# WaveGenerator.net
KiCad netlist of a schematic drawn in Altium Designer
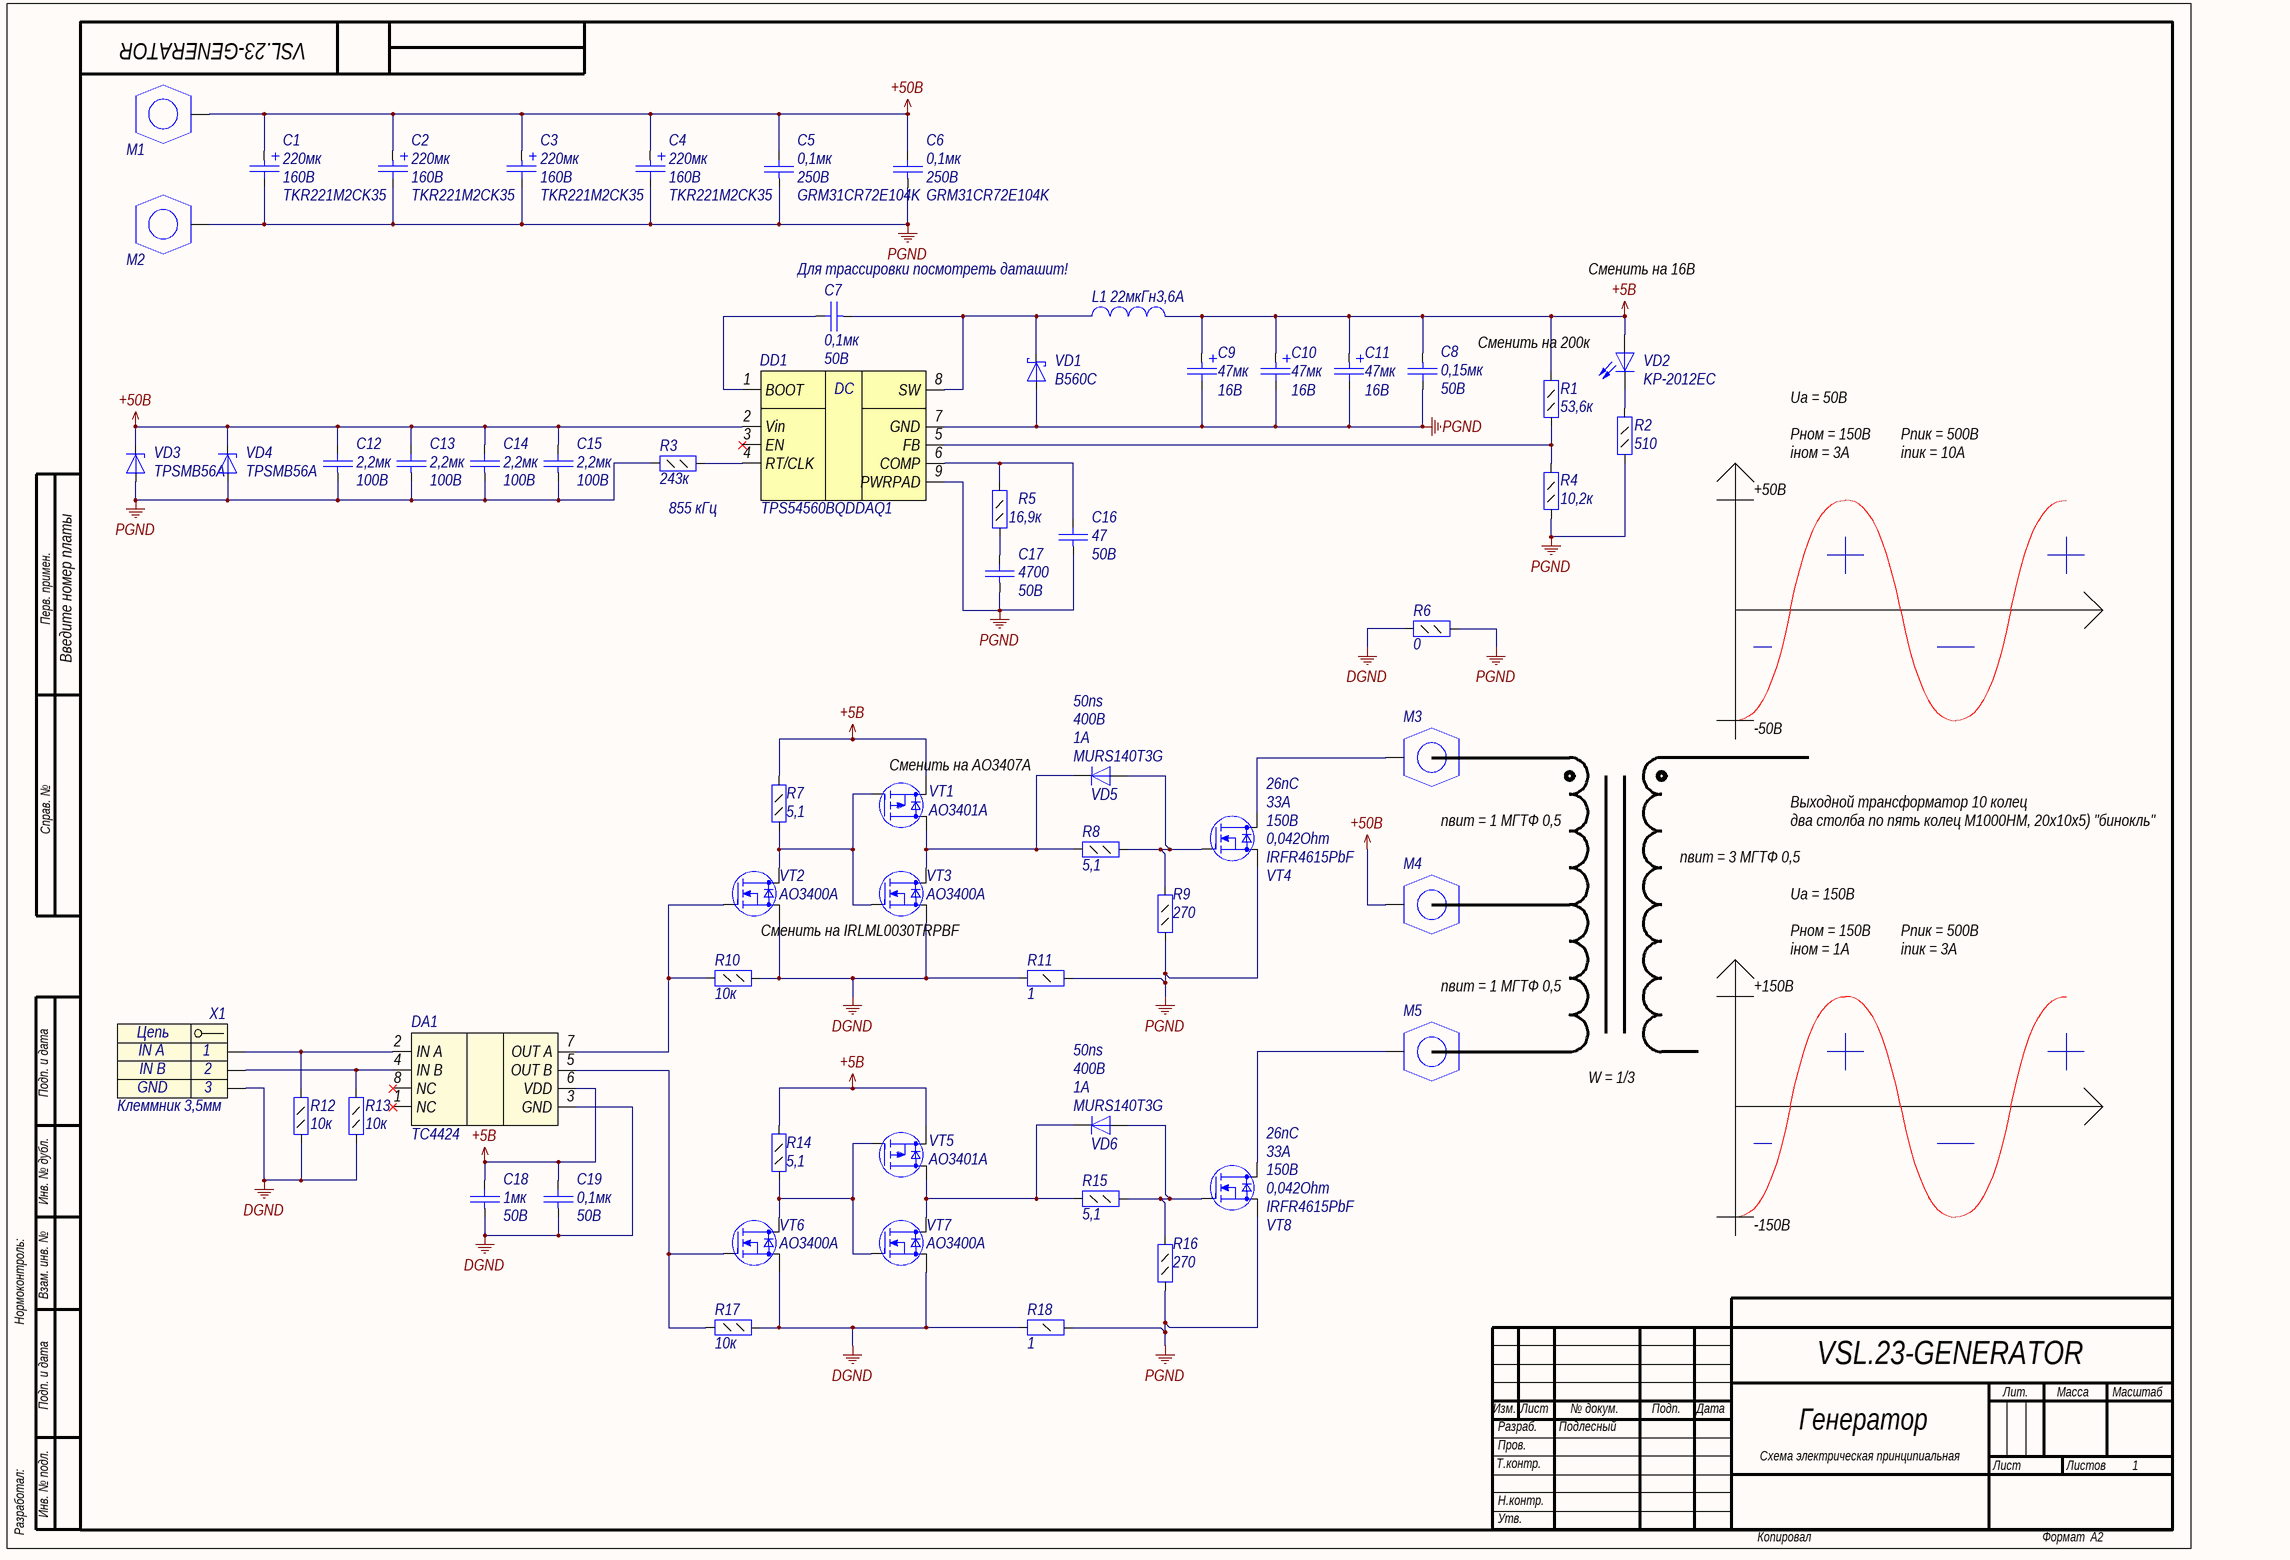
[diagram p0: WaveGenerator.SchDoc]

(export (version "E")
  (design (tool "Eeschema 10.0.6"))
  (components
    (comp (ref "C1")
      (value "220мк")
      (footprint "K50-35(16X35)_V")
      (description "Конденсатор полярный")
      (fields
        (field (name "VOLTAGE") "160B")
        (field (name "PART NUMBER") "TKR221M2CK35")
        (field (name "Comment") "Capacitor_pol")
      )
      (libsource (lib "MOP44") (part "Capacitor_pol"))
    )
    (comp (ref "C2")
      (value "220мк")
      (footprint "K50-35(16X35)_V")
      (description "Конденсатор полярный")
      (fields
        (field (name "VOLTAGE") "160B")
        (field (name "PART NUMBER") "TKR221M2CK35")
        (field (name "Comment") "Capacitor_pol")
      )
      (libsource (lib "MOP44") (part "Capacitor_pol"))
    )
    (comp (ref "C3")
      (value "220мк")
      (footprint "K50-35(16X35)_V")
      (description "Конденсатор полярный")
      (fields
        (field (name "VOLTAGE") "160B")
        (field (name "PART NUMBER") "TKR221M2CK35")
        (field (name "Comment") "Capacitor_pol")
      )
      (libsource (lib "MOP44") (part "Capacitor_pol"))
    )
    (comp (ref "C4")
      (value "220мк")
      (footprint "K50-35(16X35)_V")
      (description "Конденсатор полярный")
      (fields
        (field (name "VOLTAGE") "160B")
        (field (name "PART NUMBER") "TKR221M2CK35")
        (field (name "Comment") "Capacitor_pol")
      )
      (libsource (lib "MOP44") (part "Capacitor_pol"))
    )
    (comp (ref "C5")
      (value "0,1мк")
      (footprint "C1206")
      (description "Конденсатор")
      (fields (field (name "VOLTAGE") "250В") (field (name "PART NUMBER") "GRM31CR72E104K"))
      (libsource (lib "MOP44") (part "Capacitor"))
    )
    (comp (ref "C6")
      (value "0,1мк")
      (footprint "C1206")
      (description "Конденсатор")
      (fields (field (name "VOLTAGE") "250В") (field (name "PART NUMBER") "GRM31CR72E104K"))
      (libsource (lib "MOP44") (part "Capacitor"))
    )
    (comp (ref "C7")
      (value "0,1мк")
      (footprint "C0402")
      (description "Конденсатор")
      (fields (field (name "VOLTAGE") "50В") (field (name "PART NUMBER") "GRM155R71H104KE14D"))
      (libsource (lib "MOP44") (part "Capacitor"))
    )
    (comp (ref "C8")
      (value "0,15мк")
      (footprint "C1812")
      (description "Конденсатор")
      (fields (field (name "VOLTAGE") "50В") (field (name "PART NUMBER") "C4532C0G1H154J250KA"))
      (libsource (lib "MOP44") (part "Capacitor"))
    )
    (comp (ref "C9")
      (value "47мк")
      (footprint "TANTAL CASE C")
      (description "Конденсатор полярный")
      (fields
        (field (name "VOLTAGE") "16В")
        (field (name "PART NUMBER") "TECAP47/16VC10")
        (field (name "Comment") "Capacitor_pol")
      )
      (libsource (lib "MOP44") (part "Capacitor_pol"))
    )
    (comp (ref "C10")
      (value "47мк")
      (footprint "TANTAL CASE C")
      (description "Конденсатор полярный")
      (fields
        (field (name "VOLTAGE") "16В")
        (field (name "PART NUMBER") "TECAP47/16VC10")
        (field (name "Comment") "Capacitor_pol")
      )
      (libsource (lib "MOP44") (part "Capacitor_pol"))
    )
    (comp (ref "C11")
      (value "47мк")
      (footprint "TANTAL CASE C")
      (description "Конденсатор полярный")
      (fields
        (field (name "VOLTAGE") "16В")
        (field (name "PART NUMBER") "TECAP47/16VC10")
        (field (name "Comment") "Capacitor_pol")
      )
      (libsource (lib "MOP44") (part "Capacitor_pol"))
    )
    (comp (ref "C12")
      (value "2,2мк")
      (footprint "C1812")
      (description "Конденсатор")
      (fields (field (name "VOLTAGE") "100В") (field (name "PART NUMBER") "C4532X7R2A225M"))
      (libsource (lib "MOP44") (part "Capacitor"))
    )
    (comp (ref "C13")
      (value "2,2мк")
      (footprint "C1812")
      (description "Конденсатор")
      (fields (field (name "VOLTAGE") "100В") (field (name "PART NUMBER") "C4532X7R2A225M"))
      (libsource (lib "MOP44") (part "Capacitor"))
    )
    (comp (ref "C14")
      (value "2,2мк")
      (footprint "C1812")
      (description "Конденсатор")
      (fields (field (name "VOLTAGE") "100В") (field (name "PART NUMBER") "C4532X7R2A225M"))
      (libsource (lib "MOP44") (part "Capacitor"))
    )
    (comp (ref "C15")
      (value "2,2мк")
      (footprint "C1812")
      (description "Конденсатор")
      (fields (field (name "VOLTAGE") "100В") (field (name "PART NUMBER") "C4532X7R2A225M"))
      (libsource (lib "MOP44") (part "Capacitor"))
    )
    (comp (ref "C16")
      (value "47")
      (footprint "C0805")
      (description "Конденсатор")
      (fields (field (name "VOLTAGE") "50В") (field (name "PART NUMBER") "GRM2165C1H470JD01D"))
      (libsource (lib "MOP44") (part "Capacitor"))
    )
    (comp (ref "C17")
      (value "4700")
      (footprint "C0805")
      (description "Конденсатор")
      (fields (field (name "VOLTAGE") "50В") (field (name "PART NUMBER") "GRM216R71H472K"))
      (libsource (lib "MOP44") (part "Capacitor"))
    )
    (comp (ref "C18")
      (value "1мк")
      (footprint "C0805")
      (description "Конденсатор")
      (fields (field (name "VOLTAGE") "50B") (field (name "PART NUMBER") "GRM21BR71H105K"))
      (libsource (lib "MOP44") (part "Capacitor"))
    )
    (comp (ref "C19")
      (value "0,1мк")
      (footprint "C0805")
      (description "Конденсатор")
      (fields (field (name "VOLTAGE") "50В") (field (name "PART NUMBER") "GRM21BR71H104KA01L"))
      (libsource (lib "MOP44") (part "Capacitor"))
    )
    (comp (ref "DA1")
      (value "TC4424")
      (footprint "DIP8")
      (description "3A Dual High-Speed Power MOSFET Drivers")
      (fields (field (name "PART NUMBER") "TC4424CPA"))
      (libsource (lib "MOP44") (part "TC4424"))
    )
    (comp (ref "DD1")
      (value "TPS54560")
      (footprint "SO Powerpad8")
      (description "5-A, Wide Input Range, Step-Down Converter")
      (fields
        (field (name "PART NUMBER") "TPS54560BQDDAQ1")
        (field (name "MANUFACTURER") "Texas Instruments")
      )
      (libsource (lib "MOP44") (part "TPS54560"))
    )
    (comp (ref "L1")
      (value "22мкГн")
      (footprint "IND_12.5x12.5")
      (description "EMI Suppression Filter")
      (fields
        (field (name "RATED CURRENT") "3,6A")
        (field (name "PART NUMBER") "B82477G4223M000")
        (field (name "Comment") "Inductor")
      )
      (libsource (lib "MOP44") (part "Inductor"))
    )
    (comp (ref "M1") (value "SCREW") (footprint "SCREW2.5") (libsource (lib "MOP44") (part "SCREW")))
    (comp (ref "M2") (value "SCREW") (footprint "SCREW2.5") (libsource (lib "MOP44") (part "SCREW")))
    (comp (ref "M3") (value "SCREW") (footprint "SCREW2.5") (libsource (lib "MOP44") (part "SCREW")))
    (comp (ref "M4") (value "SCREW") (footprint "SCREW2.5") (libsource (lib "MOP44") (part "SCREW")))
    (comp (ref "M5") (value "SCREW") (footprint "SCREW2.5") (libsource (lib "MOP44") (part "SCREW")))
    (comp (ref "R1")
      (value "53,6к")
      (footprint "R0805")
      (description "Резистор")
      (fields (field (name "PART NUMBER") "RC0805FR-0753K6L") (field (name "POWER") "0,125Вт"))
      (libsource (lib "MOP44") (part "Resistor_0,125Вт"))
    )
    (comp (ref "R2")
      (value "510")
      (footprint "R0805")
      (description "Резистор")
      (fields (field (name "PART NUMBER") "RC0805FR-07510RL") (field (name "POWER") "0,125Вт"))
      (libsource (lib "MOP44") (part "Resistor_0,125Вт"))
    )
    (comp (ref "R3")
      (value "243к")
      (footprint "R0805")
      (description "Резистор")
      (fields (field (name "PART NUMBER") "RC0805FR-07243KL") (field (name "POWER") "0,125Вт"))
      (libsource (lib "") (part "Resistor_0,125Вт_2"))
    )
    (comp (ref "R4")
      (value "10,2к")
      (footprint "R0805")
      (description "Резистор")
      (fields (field (name "PART NUMBER") "RC0805FR-0710K2L") (field (name "POWER") "0,125Вт"))
      (libsource (lib "MOP44") (part "Resistor_0,125Вт"))
    )
    (comp (ref "R5")
      (value "16,9к")
      (footprint "R0805")
      (description "Резистор")
      (fields (field (name "PART NUMBER") "RC0805FR-0716K9L") (field (name "POWER") "0,125Вт"))
      (libsource (lib "MOP44") (part "Resistor_0,125Вт"))
    )
    (comp (ref "R6")
      (value "0")
      (footprint "R0805")
      (description "Резистор")
      (fields (field (name "PART NUMBER") "RC0805FR-070RL") (field (name "POWER") "0,125Вт"))
      (libsource (lib "") (part "Resistor_0,125Вт_2"))
    )
    (comp (ref "R7")
      (value "5,1")
      (footprint "R0805")
      (description "Резистор")
      (fields (field (name "PART NUMBER") "RC0805FR-075R1L") (field (name "POWER") "0,125Вт"))
      (libsource (lib "MOP44") (part "Resistor_0,125Вт"))
    )
    (comp (ref "R8")
      (value "5,1")
      (footprint "R0805")
      (description "Резистор")
      (fields (field (name "PART NUMBER") "RC0805FR-075R1L") (field (name "POWER") "0,125Вт"))
      (libsource (lib "") (part "Resistor_0,125Вт_2"))
    )
    (comp (ref "R9")
      (value "270")
      (footprint "R0805")
      (description "Резистор")
      (fields (field (name "PART NUMBER") "RC0805FR-07270RL") (field (name "POWER") "0,125Вт"))
      (libsource (lib "MOP44") (part "Resistor_0,125Вт"))
    )
    (comp (ref "R10")
      (value "10к")
      (footprint "R0805")
      (description "Резистор")
      (fields (field (name "PART NUMBER") "RC0805FR-0710KL") (field (name "POWER") "0,125Вт"))
      (libsource (lib "") (part "Resistor_0,125Вт_1"))
    )
    (comp (ref "R11")
      (value "1")
      (footprint "R1206")
      (description "Резистор")
      (fields (field (name "PART NUMBER") "RC1206FR-071RL") (field (name "POWER") "0,25Вт"))
      (libsource (lib "MOP44") (part "Resistor_0,25Вт"))
    )
    (comp (ref "R12")
      (value "10к")
      (footprint "R0805")
      (description "Резистор")
      (fields (field (name "PART NUMBER") "RC0805FR-0710KL") (field (name "POWER") "0,125Вт"))
      (libsource (lib "MOP44") (part "Resistor_0,125Вт"))
    )
    (comp (ref "R13")
      (value "10к")
      (footprint "R0805")
      (description "Резистор")
      (fields (field (name "PART NUMBER") "RC0805FR-0710KL") (field (name "POWER") "0,125Вт"))
      (libsource (lib "MOP44") (part "Resistor_0,125Вт"))
    )
    (comp (ref "R14")
      (value "5,1")
      (footprint "R0805")
      (description "Резистор")
      (fields (field (name "PART NUMBER") "RC0805FR-075R1L") (field (name "POWER") "0,125Вт"))
      (libsource (lib "MOP44") (part "Resistor_0,125Вт"))
    )
    (comp (ref "R15")
      (value "5,1")
      (footprint "R0805")
      (description "Резистор")
      (fields (field (name "PART NUMBER") "RC0805FR-075R1L") (field (name "POWER") "0,125Вт"))
      (libsource (lib "") (part "Resistor_0,125Вт_2"))
    )
    (comp (ref "R16")
      (value "270")
      (footprint "R0805")
      (description "Резистор")
      (fields (field (name "PART NUMBER") "RC0805FR-07270RL") (field (name "POWER") "0,125Вт"))
      (libsource (lib "MOP44") (part "Resistor_0,125Вт"))
    )
    (comp (ref "R17")
      (value "10к")
      (footprint "R0805")
      (description "Резистор")
      (fields (field (name "PART NUMBER") "RC0805FR-0710KL") (field (name "POWER") "0,125Вт"))
      (libsource (lib "") (part "Resistor_0,125Вт_1"))
    )
    (comp (ref "R18")
      (value "1")
      (footprint "R1206")
      (description "Резистор")
      (fields (field (name "PART NUMBER") "RC1206FR-071RL") (field (name "POWER") "0,25Вт"))
      (libsource (lib "MOP44") (part "Resistor_0,25Вт"))
    )
    (comp (ref "VD1")
      (value "DiodeSchottky")
      (footprint "SMC")
      (description "Диод Шоттки")
      (fields (field (name "PART NUMBER") "B560C"))
      (libsource (lib "MOP44") (part "DiodeSchottky"))
    )
    (comp (ref "VD2")
      (value "LED")
      (footprint "L_0805")
      (description "Светодиод")
      (fields (field (name "PART NUMBER") "KP-2012EC"))
      (libsource (lib "MOP44") (part "LED"))
    )
    (comp (ref "VD3")
      (value "DiodeZener")
      (footprint "SMB")
      (description "Cтабилитрон (лавинный выпрямительный диод) односторонний")
      (fields (field (name "PART NUMBER") "TPSMB56A"))
      (libsource (lib "MOP44") (part "DiodeZener"))
    )
    (comp (ref "VD4")
      (value "DiodeZener")
      (footprint "SMB")
      (description "Cтабилитрон (лавинный выпрямительный диод) односторонний")
      (fields (field (name "PART NUMBER") "TPSMB56A"))
      (libsource (lib "MOP44") (part "DiodeZener"))
    )
    (comp (ref "VD5")
      (value "Diode")
      (footprint "SMB")
      (description "Диод")
      (fields
        (field (name "FORWARD CURRENT") "1A")
        (field (name "BREAKDOWN VOLTAGE") "400B")
        (field (name "REVERSE RECOVERY TIME") "50ns")
        (field (name "PART NUMBER") "MURS140T3G")
      )
      (libsource (lib "MOP44") (part "Diode"))
    )
    (comp (ref "VD6")
      (value "Diode")
      (footprint "SMB")
      (description "Диод")
      (fields
        (field (name "FORWARD CURRENT") "1A")
        (field (name "BREAKDOWN VOLTAGE") "400B")
        (field (name "REVERSE RECOVERY TIME") "50ns")
        (field (name "PART NUMBER") "MURS140T3G")
      )
      (libsource (lib "MOP44") (part "Diode"))
    )
    (comp (ref "VT1")
      (value "P-MOSFET")
      (footprint "SOT23-3")
      (description "N-MOSFET")
      (fields (field (name "PART NUMBER") "AO3401A") (field (name "MANUFACTURER") "Alpha&Omega"))
      (libsource (lib "MOP44") (part "P-MOSFET"))
    )
    (comp (ref "VT2")
      (value "N-MOSFET")
      (footprint "SOT23-3")
      (fields (field (name "PART NUMBER") "AO3400A") (field (name "MANUFACTURER") "Alpha&Omega"))
      (libsource (lib "MOP44") (part "N-MOSFET"))
    )
    (comp (ref "VT3")
      (value "N-MOSFET")
      (footprint "SOT23-3")
      (fields (field (name "PART NUMBER") "AO3400A") (field (name "MANUFACTURER") "Alpha&Omega"))
      (libsource (lib "MOP44") (part "N-MOSFET"))
    )
    (comp (ref "VT4")
      (value "N-MOSFET")
      (footprint "DPAK")
      (fields
        (field (name "V DRAIN-SOURCE MAX") "150B")
        (field (name "RDS") "0,042Ohm")
        (field (name "CONTINUOUS DRAIN CURRENT") "33A")
        (field (name "TOTAL GATE CHARGE") "26nC")
        (field (name "PART NUMBER") "IRFR4615PbF")
        (field (name "MANUFACTURER") "International Rectifier")
      )
      (libsource (lib "MOP44") (part "N-MOSFET"))
    )
    (comp (ref "VT5")
      (value "P-MOSFET")
      (footprint "SOT23-3")
      (description "N-MOSFET")
      (fields (field (name "PART NUMBER") "AO3401A") (field (name "MANUFACTURER") "Alpha&Omega"))
      (libsource (lib "MOP44") (part "P-MOSFET"))
    )
    (comp (ref "VT6")
      (value "N-MOSFET")
      (footprint "SOT23-3")
      (fields (field (name "PART NUMBER") "AO3400A") (field (name "MANUFACTURER") "Alpha&Omega"))
      (libsource (lib "MOP44") (part "N-MOSFET"))
    )
    (comp (ref "VT7")
      (value "N-MOSFET")
      (footprint "SOT23-3")
      (fields (field (name "PART NUMBER") "AO3400A") (field (name "MANUFACTURER") "Alpha&Omega"))
      (libsource (lib "MOP44") (part "N-MOSFET"))
    )
    (comp (ref "VT8")
      (value "N-MOSFET")
      (footprint "DPAK")
      (fields
        (field (name "V DRAIN-SOURCE MAX") "150B")
        (field (name "RDS") "0,042Ohm")
        (field (name "CONTINUOUS DRAIN CURRENT") "33A")
        (field (name "TOTAL GATE CHARGE") "26nC")
        (field (name "PART NUMBER") "IRFR4615PbF")
        (field (name "MANUFACTURER") "International Rectifier")
      )
      (libsource (lib "MOP44") (part "N-MOSFET"))
    )
    (comp (ref "X1")
      (value "Клеммник 3,5мм")
      (footprint "TERMINAL-3WAY-3.5MM")
      (description "Разъем - 3 конт. клеммник")
      (libsource (lib "MOP44") (part "Header_3_trm"))
    )
  )
  (nets
    (net (code "1") (name "+5B") (class "Default")
      (node (ref "C10") (pin "1") (pinfunction "1_1") (pintype "passive"))
      (node (ref "C11") (pin "1") (pinfunction "1_1") (pintype "passive"))
      (node (ref "C18") (pin "2") (pinfunction "2_2") (pintype "passive"))
      (node (ref "C19") (pin "2") (pinfunction "2_2") (pintype "passive"))
      (node (ref "C8") (pin "1") (pinfunction "1_1") (pintype "passive"))
      (node (ref "C9") (pin "1") (pinfunction "1_1") (pintype "passive"))
      (node (ref "DA1") (pin "6") (pinfunction "VDD_6") (pintype "passive"))
      (node (ref "L1") (pin "2") (pinfunction "2_2") (pintype "passive"))
      (node (ref "R1") (pin "2") (pinfunction "2_2") (pintype "passive"))
      (node (ref "R14") (pin "2") (pinfunction "2_2") (pintype "passive"))
      (node (ref "R7") (pin "2") (pinfunction "2_2") (pintype "passive"))
      (node (ref "VD2") (pin "2") (pinfunction "A_2") (pintype "passive"))
      (node (ref "VT1") (pin "3") (pinfunction "S_3") (pintype "passive"))
      (node (ref "VT5") (pin "3") (pinfunction "S_3") (pintype "passive"))
    )
    (net (code "2") (name "+50B") (class "Default")
      (node (ref "C1") (pin "1") (pinfunction "1_1") (pintype "passive"))
      (node (ref "C12") (pin "2") (pinfunction "2_2") (pintype "passive"))
      (node (ref "C13") (pin "2") (pinfunction "2_2") (pintype "passive"))
      (node (ref "C14") (pin "2") (pinfunction "2_2") (pintype "passive"))
      (node (ref "C15") (pin "2") (pinfunction "2_2") (pintype "passive"))
      (node (ref "C2") (pin "1") (pinfunction "1_1") (pintype "passive"))
      (node (ref "C3") (pin "1") (pinfunction "1_1") (pintype "passive"))
      (node (ref "C4") (pin "1") (pinfunction "1_1") (pintype "passive"))
      (node (ref "C5") (pin "2") (pinfunction "2_2") (pintype "passive"))
      (node (ref "C6") (pin "2") (pinfunction "2_2") (pintype "passive"))
      (node (ref "DD1") (pin "2") (pinfunction "Vin_2") (pintype "passive"))
      (node (ref "M1") (pin "1") (pinfunction "1_1") (pintype "passive"))
      (node (ref "M4") (pin "1") (pinfunction "1_1") (pintype "passive"))
      (node (ref "VD3") (pin "1") (pinfunction "K_1") (pintype "passive"))
      (node (ref "VD4") (pin "1") (pinfunction "K_1") (pintype "passive"))
    )
    (net (code "3") (name "DGND") (class "Default")
      (node (ref "C18") (pin "1") (pinfunction "1_1") (pintype "passive"))
      (node (ref "C19") (pin "1") (pinfunction "1_1") (pintype "passive"))
      (node (ref "DA1") (pin "3") (pinfunction "GND_3") (pintype "passive"))
      (node (ref "R10") (pin "1") (pinfunction "1_1") (pintype "passive"))
      (node (ref "R11") (pin "1") (pinfunction "1_1") (pintype "passive"))
      (node (ref "R12") (pin "1") (pinfunction "1_1") (pintype "passive"))
      (node (ref "R13") (pin "1") (pinfunction "1_1") (pintype "passive"))
      (node (ref "R17") (pin "1") (pinfunction "1_1") (pintype "passive"))
      (node (ref "R18") (pin "1") (pinfunction "1_1") (pintype "passive"))
      (node (ref "R6") (pin "1") (pinfunction "1_1") (pintype "passive"))
      (node (ref "VT2") (pin "3") (pinfunction "S_3") (pintype "passive"))
      (node (ref "VT3") (pin "3") (pinfunction "S_3") (pintype "passive"))
      (node (ref "VT6") (pin "3") (pinfunction "S_3") (pintype "passive"))
      (node (ref "VT7") (pin "3") (pinfunction "S_3") (pintype "passive"))
      (node (ref "X1") (pin "3") (pinfunction "3_3") (pintype "passive"))
    )
    (net (code "4") (name "Net-(C17-Pad2)") (class "Default")
      (node (ref "C17") (pin "2") (pinfunction "2_2") (pintype "passive"))
      (node (ref "R5") (pin "1") (pinfunction "1_1") (pintype "passive"))
    )
    (net (code "5") (name "Net-(DA1-IN_A)") (class "Default")
      (node (ref "DA1") (pin "2") (pinfunction "IN_A_2") (pintype "passive"))
      (node (ref "R12") (pin "2") (pinfunction "2_2") (pintype "passive"))
      (node (ref "X1") (pin "1") (pinfunction "1_1") (pintype "passive"))
    )
    (net (code "6") (name "Net-(DA1-IN_B)") (class "Default")
      (node (ref "DA1") (pin "4") (pinfunction "IN_B_4") (pintype "passive"))
      (node (ref "R13") (pin "2") (pinfunction "2_2") (pintype "passive"))
      (node (ref "X1") (pin "2") (pinfunction "2_2") (pintype "passive"))
    )
    (net (code "7") (name "Net-(DA1-OUT_A)") (class "Default")
      (node (ref "DA1") (pin "7") (pinfunction "OUT_A_7") (pintype "passive"))
      (node (ref "R10") (pin "2") (pinfunction "2_2") (pintype "passive"))
      (node (ref "VT2") (pin "1") (pinfunction "G_1") (pintype "passive"))
    )
    (net (code "8") (name "Net-(DA1-OUT_B)") (class "Default")
      (node (ref "DA1") (pin "5") (pinfunction "OUT_B_5") (pintype "passive"))
      (node (ref "R17") (pin "2") (pinfunction "2_2") (pintype "passive"))
      (node (ref "VT6") (pin "1") (pinfunction "G_1") (pintype "passive"))
    )
    (net (code "9") (name "Net-(DD1-BOOT)") (class "Default")
      (node (ref "C7") (pin "2") (pinfunction "2_2") (pintype "passive"))
      (node (ref "DD1") (pin "1") (pinfunction "BOOT_1") (pintype "passive"))
    )
    (net (code "10") (name "Net-(DD1-COMP)") (class "Default")
      (node (ref "C16") (pin "2") (pinfunction "2_2") (pintype "passive"))
      (node (ref "DD1") (pin "6") (pinfunction "COMP_6") (pintype "passive"))
      (node (ref "R5") (pin "2") (pinfunction "2_2") (pintype "passive"))
    )
    (net (code "11") (name "Net-(DD1-FB)") (class "Default")
      (node (ref "DD1") (pin "5") (pinfunction "FB_5") (pintype "passive"))
      (node (ref "R1") (pin "1") (pinfunction "1_1") (pintype "passive"))
      (node (ref "R4") (pin "2") (pinfunction "2_2") (pintype "passive"))
    )
    (net (code "12") (name "Net-(DD1-RT{slash}CLK)") (class "Default")
      (node (ref "DD1") (pin "4") (pinfunction "RT/CLK_4") (pintype "passive"))
      (node (ref "R3") (pin "2") (pinfunction "2_2") (pintype "passive"))
    )
    (net (code "13") (name "Net-(DD1-SW)") (class "Default")
      (node (ref "C7") (pin "1") (pinfunction "1_1") (pintype "passive"))
      (node (ref "DD1") (pin "8") (pinfunction "SW_8") (pintype "passive"))
      (node (ref "L1") (pin "1") (pinfunction "1_1") (pintype "passive"))
      (node (ref "VD1") (pin "1") (pinfunction "K_1") (pintype "passive"))
    )
    (net (code "14") (name "Net-(VD2-K)") (class "Default")
      (node (ref "R2") (pin "2") (pinfunction "2_2") (pintype "passive"))
      (node (ref "VD2") (pin "1") (pinfunction "K_1") (pintype "passive"))
    )
    (net (code "15") (name "Net-(VD5-A)") (class "Default")
      (node (ref "R8") (pin "2") (pinfunction "2_2") (pintype "passive"))
      (node (ref "R9") (pin "2") (pinfunction "2_2") (pintype "passive"))
      (node (ref "VD5") (pin "2") (pinfunction "A_2") (pintype "passive"))
      (node (ref "VT4") (pin "1") (pinfunction "G_1") (pintype "passive"))
    )
    (net (code "16") (name "Net-(VD5-K)") (class "Default")
      (node (ref "R8") (pin "1") (pinfunction "1_1") (pintype "passive"))
      (node (ref "VD5") (pin "1") (pinfunction "K_1") (pintype "passive"))
      (node (ref "VT1") (pin "2") (pinfunction "D_2") (pintype "passive"))
      (node (ref "VT3") (pin "2") (pinfunction "D_2") (pintype "passive"))
    )
    (net (code "17") (name "Net-(VD6-A)") (class "Default")
      (node (ref "R15") (pin "2") (pinfunction "2_2") (pintype "passive"))
      (node (ref "R16") (pin "2") (pinfunction "2_2") (pintype "passive"))
      (node (ref "VD6") (pin "2") (pinfunction "A_2") (pintype "passive"))
      (node (ref "VT8") (pin "1") (pinfunction "G_1") (pintype "passive"))
    )
    (net (code "18") (name "Net-(VD6-K)") (class "Default")
      (node (ref "R15") (pin "1") (pinfunction "1_1") (pintype "passive"))
      (node (ref "VD6") (pin "1") (pinfunction "K_1") (pintype "passive"))
      (node (ref "VT5") (pin "2") (pinfunction "D_2") (pintype "passive"))
      (node (ref "VT7") (pin "2") (pinfunction "D_2") (pintype "passive"))
    )
    (net (code "19") (name "Net-(VT1-G)") (class "Default")
      (node (ref "R7") (pin "1") (pinfunction "1_1") (pintype "passive"))
      (node (ref "VT1") (pin "1") (pinfunction "G_1") (pintype "passive"))
      (node (ref "VT2") (pin "2") (pinfunction "D_2") (pintype "passive"))
      (node (ref "VT3") (pin "1") (pinfunction "G_1") (pintype "passive"))
    )
    (net (code "20") (name "Net-(VT4-D)") (class "Default")
      (node (ref "M3") (pin "1") (pinfunction "1_1") (pintype "passive"))
      (node (ref "VT4") (pin "2") (pinfunction "D_2") (pintype "passive"))
    )
    (net (code "21") (name "Net-(VT5-G)") (class "Default")
      (node (ref "R14") (pin "1") (pinfunction "1_1") (pintype "passive"))
      (node (ref "VT5") (pin "1") (pinfunction "G_1") (pintype "passive"))
      (node (ref "VT6") (pin "2") (pinfunction "D_2") (pintype "passive"))
      (node (ref "VT7") (pin "1") (pinfunction "G_1") (pintype "passive"))
    )
    (net (code "22") (name "Net-(VT8-D)") (class "Default")
      (node (ref "M5") (pin "1") (pinfunction "1_1") (pintype "passive"))
      (node (ref "VT8") (pin "2") (pinfunction "D_2") (pintype "passive"))
    )
    (net (code "23") (name "PGND") (class "Default")
      (node (ref "C1") (pin "2") (pinfunction "2_2") (pintype "passive"))
      (node (ref "C10") (pin "2") (pinfunction "2_2") (pintype "passive"))
      (node (ref "C11") (pin "2") (pinfunction "2_2") (pintype "passive"))
      (node (ref "C12") (pin "1") (pinfunction "1_1") (pintype "passive"))
      (node (ref "C13") (pin "1") (pinfunction "1_1") (pintype "passive"))
      (node (ref "C14") (pin "1") (pinfunction "1_1") (pintype "passive"))
      (node (ref "C15") (pin "1") (pinfunction "1_1") (pintype "passive"))
      (node (ref "C16") (pin "1") (pinfunction "1_1") (pintype "passive"))
      (node (ref "C17") (pin "1") (pinfunction "1_1") (pintype "passive"))
      (node (ref "C2") (pin "2") (pinfunction "2_2") (pintype "passive"))
      (node (ref "C3") (pin "2") (pinfunction "2_2") (pintype "passive"))
      (node (ref "C4") (pin "2") (pinfunction "2_2") (pintype "passive"))
      (node (ref "C5") (pin "1") (pinfunction "1_1") (pintype "passive"))
      (node (ref "C6") (pin "1") (pinfunction "1_1") (pintype "passive"))
      (node (ref "C8") (pin "2") (pinfunction "2_2") (pintype "passive"))
      (node (ref "C9") (pin "2") (pinfunction "2_2") (pintype "passive"))
      (node (ref "DD1") (pin "7") (pinfunction "GND_7") (pintype "passive"))
      (node (ref "DD1") (pin "9") (pinfunction "PWRPAD_9") (pintype "passive"))
      (node (ref "M2") (pin "1") (pinfunction "1_1") (pintype "passive"))
      (node (ref "R11") (pin "2") (pinfunction "2_2") (pintype "passive"))
      (node (ref "R16") (pin "1") (pinfunction "1_1") (pintype "passive"))
      (node (ref "R18") (pin "2") (pinfunction "2_2") (pintype "passive"))
      (node (ref "R2") (pin "1") (pinfunction "1_1") (pintype "passive"))
      (node (ref "R3") (pin "1") (pinfunction "1_1") (pintype "passive"))
      (node (ref "R4") (pin "1") (pinfunction "1_1") (pintype "passive"))
      (node (ref "R6") (pin "2") (pinfunction "2_2") (pintype "passive"))
      (node (ref "R9") (pin "1") (pinfunction "1_1") (pintype "passive"))
      (node (ref "VD1") (pin "2") (pinfunction "A_2") (pintype "passive"))
      (node (ref "VD3") (pin "2") (pinfunction "A_2") (pintype "passive"))
      (node (ref "VD4") (pin "2") (pinfunction "A_2") (pintype "passive"))
      (node (ref "VT4") (pin "3") (pinfunction "S_3") (pintype "passive"))
      (node (ref "VT8") (pin "3") (pinfunction "S_3") (pintype "passive"))
    )
    (net (code "24") (name "unconnected-(DA1-NC-Pad1)") (class "Default")
      (node (ref "DA1") (pin "1") (pinfunction "NC_1") (pintype "passive+no_connect"))
    )
    (net (code "25") (name "unconnected-(DA1-NC-Pad8)") (class "Default")
      (node (ref "DA1") (pin "8") (pinfunction "NC_8") (pintype "passive+no_connect"))
    )
    (net (code "26") (name "unconnected-(DD1-EN-Pad3)") (class "Default")
      (node (ref "DD1") (pin "3") (pinfunction "EN_3") (pintype "passive+no_connect"))
    )
  )
)
